# PCBFeeder_B_Board.net
KiCad netlist of a schematic drawn in EAGLE
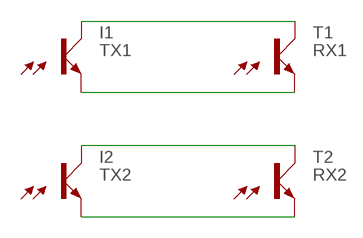
[diagram p0: schematic, sheet 1]

(export (version "E")
  (design (tool "Eeschema 10.0.6"))
  (components
    (comp (ref "I1")
      (value "TX1")
      (footprint "eagle-import:DIODE_BREAKOUT")
      (libsource (lib "eagle-import") (part "LTR-4206E"))
    )
    (comp (ref "I2")
      (value "TX2")
      (footprint "eagle-import:DIODE_BREAKOUT")
      (libsource (lib "eagle-import") (part "LTR-4206E"))
    )
    (comp (ref "T1")
      (value "RX1")
      (footprint "eagle-import:VEMT2020_PHOTOTRANSISTOR")
      (libsource (lib "eagle-import") (part "VEMT_2020_PHOTOTRANSISTOR"))
    )
    (comp (ref "T2")
      (value "RX2")
      (footprint "eagle-import:VEMT2020_PHOTOTRANSISTOR")
      (libsource (lib "eagle-import") (part "VEMT_2020_PHOTOTRANSISTOR"))
    )
  )
  (nets
    (net (code "1") (name "Net-(I1-PadA)") (class "Default")
      (node (ref "I1") (pin "A") (pinfunction "A_A") (pintype "passive"))
      (node (ref "T1") (pin "A") (pinfunction "A_A") (pintype "passive"))
    )
    (net (code "2") (name "Net-(I1-PadC)") (class "Default")
      (node (ref "I1") (pin "C") (pinfunction "C_C") (pintype "passive"))
      (node (ref "T1") (pin "C") (pinfunction "C_C") (pintype "passive"))
    )
    (net (code "3") (name "Net-(I2-PadA)") (class "Default")
      (node (ref "I2") (pin "A") (pinfunction "A_A") (pintype "passive"))
      (node (ref "T2") (pin "A") (pinfunction "A_A") (pintype "passive"))
    )
    (net (code "4") (name "Net-(I2-PadC)") (class "Default")
      (node (ref "I2") (pin "C") (pinfunction "C_C") (pintype "passive"))
      (node (ref "T2") (pin "C") (pinfunction "C_C") (pintype "passive"))
    )
  )
)
